# BLE.net
KiCad netlist of a schematic drawn in Altium Designer
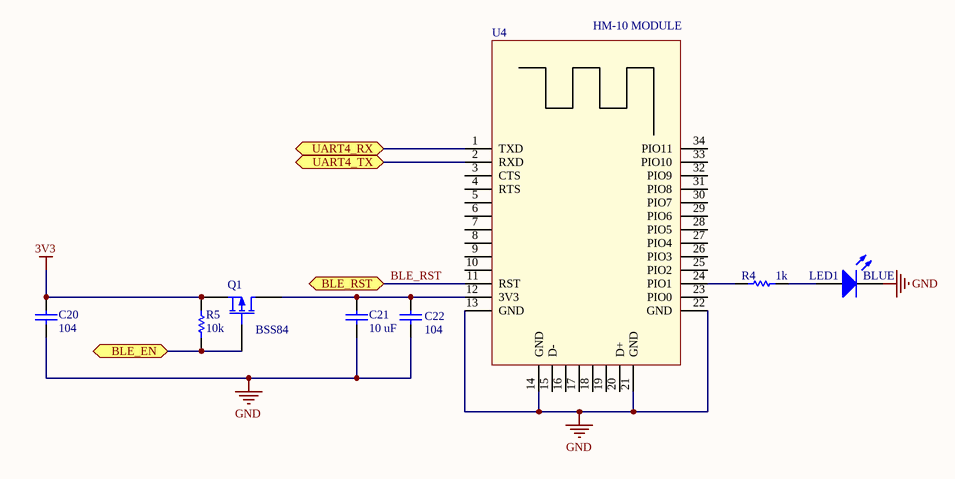
[diagram p0: BLE.SchDoc]

(export (version "E")
  (design (tool "Eeschema 10.0.6"))
  (components
    (comp (ref "C20")
      (value "104")
      (footprint "C0603")
      (description "CAP CER 0.1UF 16V Y5V 0402")
      (fields
        (field (name "MANUFACTURER") "Yageo")
        (field (name "DIGI-KEY PART NUMBER") "311-1047-1-ND")
        (field (name "PUBLISHER") "Altium Limited")
      )
      (libsource (lib "RobotClub") (part "Cap_SMT"))
    )
    (comp (ref "C21")
      (value "10 uF")
      (footprint "C1210")
      (description "CAP CER 0.1UF 16V Y5V 0402")
      (fields
        (field (name "MANUFACTURER") "Yageo")
        (field (name "DIGI-KEY PART NUMBER") "311-1047-1-ND")
        (field (name "PUBLISHER") "Altium Limited")
      )
      (libsource (lib "RobotClub") (part "Cap_SMT"))
    )
    (comp (ref "C22")
      (value "104")
      (footprint "C0603")
      (description "CAP CER 0.1UF 16V Y5V 0402")
      (fields
        (field (name "MANUFACTURER") "Yageo")
        (field (name "DIGI-KEY PART NUMBER") "311-1047-1-ND")
        (field (name "PUBLISHER") "Altium Limited")
      )
      (libsource (lib "RobotClub") (part "Cap_SMT"))
    )
    (comp (ref "LED1")
      (value "BLUE")
      (footprint "SM/LED_0603")
      (description "LED GREEN 0.2MM 13MCD 0402 SMD")
      (fields
        (field (name "DIGI-KEY PART NUMBER") "511-1592-2-ND")
        (field (name "MANUFACTURER") "Lite-On Inc")
        (field (name "PUBLISHER") "Altium Limited")
      )
      (libsource (lib "RobotClub") (part "LED"))
    )
    (comp (ref "Q1")
      (value "BSS84")
      (footprint "SOT23-3")
      (description "MOSFET P-CH 50V 130MA SOT23-3")
      (fields
        (field (name "DIGI-KEY PART NUMBER") "BSS84-FDITR-ND")
        (field (name "MANUFACTURER") "Diodes Inc")
        (field (name "PUBLISHER") "Altium Limited")
      )
      (libsource (lib "RobotClub") (part "MOSFET-P GSD"))
    )
    (comp (ref "R4")
      (value "1k")
      (footprint "R0603")
      (description "Resistor SMD 1%")
      (fields
        (field (name "DIGI-KEY PART NUMBER") "P3.24KLTR-ND")
        (field (name "MANUFACTURER") "Panasonic Electronic Components")
        (field (name "PUBLISHER") "Altium Limited")
      )
      (libsource (lib "RobotClub") (part "R_SMD1"))
    )
    (comp (ref "R5")
      (value "10k")
      (footprint "R0603")
      (description "Resistor SMD 5%")
      (fields
        (field (name "DIGI-KEY PART NUMBER") "P3.24KLTR-ND")
        (field (name "MANUFACTURER") "Panasonic Electronic Components")
        (field (name "PUBLISHER") "Altium Limited")
      )
      (libsource (lib "RobotClub") (part "R_SMD5"))
    )
    (comp (ref "U4")
      (value "HM-10 MODULE")
      (footprint "HC-05 BREAKOUT")
      (libsource (lib "RobotClub") (part "HM-10 MODULE"))
    )
  )
  (nets
    (net (code "1") (name "/BLE_EN") (class "Default")
      (node (ref "Q1") (pin "1") (pinfunction "G_1") (pintype "passive"))
      (node (ref "R5") (pin "2") (pinfunction "2_2") (pintype "passive"))
    )
    (net (code "2") (name "/BLE_RST") (class "Default")
      (node (ref "U4") (pin "11") (pinfunction "RST_11") (pintype "passive"))
    )
    (net (code "3") (name "/UART4_RX") (class "Default")
      (node (ref "U4") (pin "1") (pinfunction "TXD_1") (pintype "passive"))
    )
    (net (code "4") (name "/UART4_TX") (class "Default")
      (node (ref "U4") (pin "2") (pinfunction "RXD_2") (pintype "passive"))
    )
    (net (code "5") (name "3V3") (class "Default")
      (node (ref "C20") (pin "2") (pinfunction "2_2") (pintype "passive"))
      (node (ref "Q1") (pin "2") (pinfunction "S_2") (pintype "passive"))
      (node (ref "R5") (pin "1") (pinfunction "1_1") (pintype "passive"))
    )
    (net (code "6") (name "GND") (class "Default")
      (node (ref "C20") (pin "1") (pinfunction "1_1") (pintype "passive"))
      (node (ref "C21") (pin "1") (pinfunction "1_1") (pintype "passive"))
      (node (ref "C22") (pin "1") (pinfunction "1_1") (pintype "passive"))
      (node (ref "LED1") (pin "2") (pinfunction "K_2") (pintype "passive"))
      (node (ref "U4") (pin "13") (pinfunction "GND_13") (pintype "passive"))
      (node (ref "U4") (pin "14") (pinfunction "GND_14") (pintype "passive"))
      (node (ref "U4") (pin "21") (pinfunction "GND_21") (pintype "passive"))
      (node (ref "U4") (pin "22") (pinfunction "GND_22") (pintype "passive"))
    )
    (net (code "7") (name "Net-(LED1-A)") (class "Default")
      (node (ref "LED1") (pin "1") (pinfunction "A_1") (pintype "passive"))
      (node (ref "R4") (pin "2") (pinfunction "2_2") (pintype "passive"))
    )
    (net (code "8") (name "Net-(Q1-D)") (class "Default")
      (node (ref "C21") (pin "2") (pinfunction "2_2") (pintype "passive"))
      (node (ref "C22") (pin "2") (pinfunction "2_2") (pintype "passive"))
      (node (ref "Q1") (pin "3") (pinfunction "D_3") (pintype "passive"))
      (node (ref "U4") (pin "12") (pinfunction "3V3_12") (pintype "passive"))
    )
    (net (code "9") (name "Net-(U4-PIO1)") (class "Default")
      (node (ref "R4") (pin "1") (pinfunction "1_1") (pintype "passive"))
      (node (ref "U4") (pin "24") (pinfunction "PIO1_24") (pintype "passive"))
    )
    (net (code "10") (name "unconnected-(U4-CTS-Pad3)") (class "Default")
      (node (ref "U4") (pin "3") (pinfunction "CTS_3") (pintype "passive"))
    )
    (net (code "11") (name "unconnected-(U4-D+-Pad20)") (class "Default")
      (node (ref "U4") (pin "20") (pinfunction "D+_20") (pintype "passive"))
    )
    (net (code "12") (name "unconnected-(U4-D--Pad15)") (class "Default")
      (node (ref "U4") (pin "15") (pinfunction "D-_15") (pintype "passive"))
    )
    (net (code "13") (name "unconnected-(U4-PIO0-Pad23)") (class "Default")
      (node (ref "U4") (pin "23") (pinfunction "PIO0_23") (pintype "passive"))
    )
    (net (code "14") (name "unconnected-(U4-PIO2-Pad25)") (class "Default")
      (node (ref "U4") (pin "25") (pinfunction "PIO2_25") (pintype "passive"))
    )
    (net (code "15") (name "unconnected-(U4-PIO3-Pad26)") (class "Default")
      (node (ref "U4") (pin "26") (pinfunction "PIO3_26") (pintype "passive"))
    )
    (net (code "16") (name "unconnected-(U4-PIO4-Pad27)") (class "Default")
      (node (ref "U4") (pin "27") (pinfunction "PIO4_27") (pintype "passive"))
    )
    (net (code "17") (name "unconnected-(U4-PIO5-Pad28)") (class "Default")
      (node (ref "U4") (pin "28") (pinfunction "PIO5_28") (pintype "passive"))
    )
    (net (code "18") (name "unconnected-(U4-PIO6-Pad29)") (class "Default")
      (node (ref "U4") (pin "29") (pinfunction "PIO6_29") (pintype "passive"))
    )
    (net (code "19") (name "unconnected-(U4-PIO7-Pad30)") (class "Default")
      (node (ref "U4") (pin "30") (pinfunction "PIO7_30") (pintype "passive"))
    )
    (net (code "20") (name "unconnected-(U4-PIO8-Pad31)") (class "Default")
      (node (ref "U4") (pin "31") (pinfunction "PIO8_31") (pintype "passive"))
    )
    (net (code "21") (name "unconnected-(U4-PIO9-Pad32)") (class "Default")
      (node (ref "U4") (pin "32") (pinfunction "PIO9_32") (pintype "passive"))
    )
    (net (code "22") (name "unconnected-(U4-PIO10-Pad33)") (class "Default")
      (node (ref "U4") (pin "33") (pinfunction "PIO10_33") (pintype "passive"))
    )
    (net (code "23") (name "unconnected-(U4-PIO11-Pad34)") (class "Default")
      (node (ref "U4") (pin "34") (pinfunction "PIO11_34") (pintype "passive"))
    )
    (net (code "24") (name "unconnected-(U4-Pad5)") (class "Default")
      (node (ref "U4") (pin "5") (pintype "passive"))
    )
    (net (code "25") (name "unconnected-(U4-Pad6)") (class "Default")
      (node (ref "U4") (pin "6") (pintype "passive"))
    )
    (net (code "26") (name "unconnected-(U4-Pad7)") (class "Default")
      (node (ref "U4") (pin "7") (pintype "passive"))
    )
    (net (code "27") (name "unconnected-(U4-Pad8)") (class "Default")
      (node (ref "U4") (pin "8") (pintype "passive"))
    )
    (net (code "28") (name "unconnected-(U4-Pad9)") (class "Default")
      (node (ref "U4") (pin "9") (pintype "passive"))
    )
    (net (code "29") (name "unconnected-(U4-Pad10)") (class "Default")
      (node (ref "U4") (pin "10") (pintype "passive"))
    )
    (net (code "30") (name "unconnected-(U4-Pad16)") (class "Default")
      (node (ref "U4") (pin "16") (pintype "passive"))
    )
    (net (code "31") (name "unconnected-(U4-Pad17)") (class "Default")
      (node (ref "U4") (pin "17") (pintype "passive"))
    )
    (net (code "32") (name "unconnected-(U4-Pad18)") (class "Default")
      (node (ref "U4") (pin "18") (pintype "passive"))
    )
    (net (code "33") (name "unconnected-(U4-Pad19)") (class "Default")
      (node (ref "U4") (pin "19") (pintype "passive"))
    )
    (net (code "34") (name "unconnected-(U4-RTS-Pad4)") (class "Default")
      (node (ref "U4") (pin "4") (pinfunction "RTS_4") (pintype "passive"))
    )
  )
)
